# EWSII.net
KiCad netlist of a schematic drawn in EAGLE
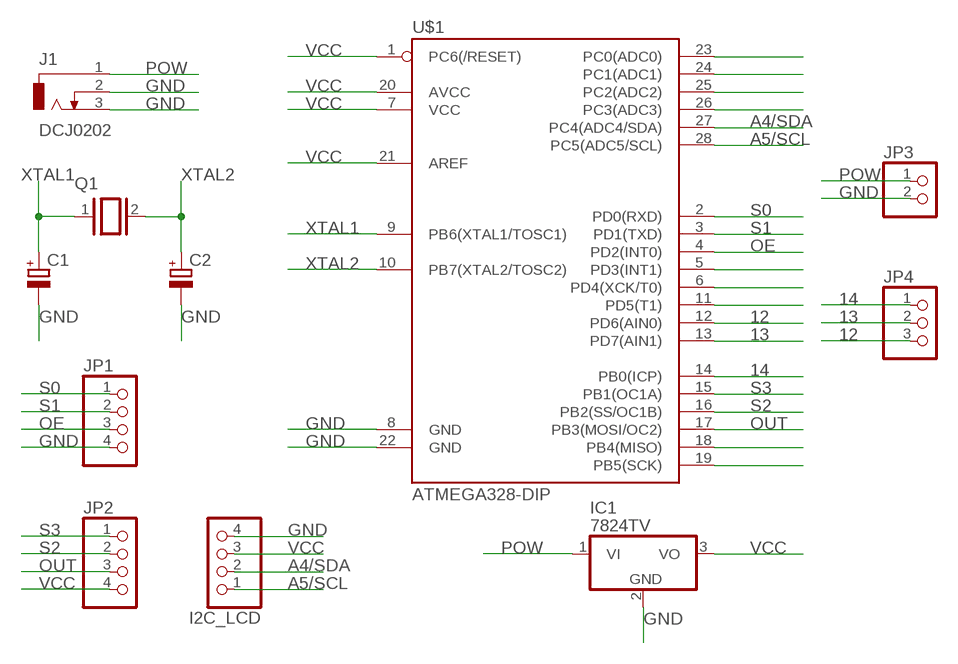
[diagram p0: schematic, sheet 1]

(export (version "E")
  (design (tool "Eeschema 10.0.6"))
  (components
    (comp (ref "C1")
      (value "CPOL-EUE2-5")
      (footprint "eagle-import:E2-5")
      (libsource (lib "eagle-import") (part "CPOL-EUE2-5"))
    )
    (comp (ref "C2")
      (value "CPOL-EUE2-5")
      (footprint "eagle-import:E2-5")
      (libsource (lib "eagle-import") (part "CPOL-EUE2-5"))
    )
    (comp (ref "I2C_LCD")
      (value "PINHD-1X4")
      (footprint "eagle-import:1X04")
      (libsource (lib "eagle-import") (part "PINHD-1X4"))
    )
    (comp (ref "IC1")
      (value "7824TV")
      (footprint "eagle-import:TO220V")
      (libsource (lib "eagle-import") (part "78TV24"))
    )
    (comp (ref "J1")
      (value "DCJ0202")
      (footprint "eagle-import:DCJ0202")
      (libsource (lib "eagle-import") (part "DCJ0202"))
    )
    (comp (ref "JP1")
      (value "PINHD-1X4")
      (footprint "eagle-import:1X04")
      (libsource (lib "eagle-import") (part "PINHD-1X4"))
    )
    (comp (ref "JP2")
      (value "PINHD-1X4")
      (footprint "eagle-import:1X04")
      (libsource (lib "eagle-import") (part "PINHD-1X4"))
    )
    (comp (ref "JP3")
      (value "PINHD-1X2")
      (footprint "eagle-import:1X02")
      (libsource (lib "eagle-import") (part "PINHD-1X2"))
    )
    (comp (ref "JP4")
      (value "PINHD-1X3")
      (footprint "eagle-import:1X03")
      (libsource (lib "eagle-import") (part "PINHD-1X3"))
    )
    (comp (ref "Q1")
      (value "XTAL/S")
      (footprint "eagle-import:QS")
      (libsource (lib "eagle-import") (part "XTAL/S"))
    )
    (comp (ref "U$1")
      (value "ATMEGA328-DIP")
      (footprint "eagle-import:DIP1016W53P254L3466H457Q28B")
      (libsource (lib "eagle-import") (part "ATMEGA328-DIP"))
    )
  )
  (nets
    (net (code "1") (name "/12") (class "Default")
      (node (ref "JP4") (pin "3") (pinfunction "3_3") (pintype "passive"))
      (node (ref "U$1") (pin "12") (pinfunction "PD6(AIN0)_12") (pintype "bidirectional"))
    )
    (net (code "2") (name "/13") (class "Default")
      (node (ref "JP4") (pin "2") (pinfunction "2_2") (pintype "passive"))
      (node (ref "U$1") (pin "13") (pinfunction "PD7(AIN1)_13") (pintype "bidirectional"))
    )
    (net (code "3") (name "/14") (class "Default")
      (node (ref "JP4") (pin "1") (pinfunction "1_1") (pintype "passive"))
      (node (ref "U$1") (pin "14") (pinfunction "PB0(ICP)_14") (pintype "bidirectional"))
    )
    (net (code "4") (name "/A4{slash}SDA") (class "Default")
      (node (ref "I2C_LCD") (pin "2") (pinfunction "2_2") (pintype "passive"))
      (node (ref "U$1") (pin "27") (pinfunction "PC4(ADC4/SDA)_27") (pintype "bidirectional"))
    )
    (net (code "5") (name "/A5{slash}SCL") (class "Default")
      (node (ref "I2C_LCD") (pin "1") (pinfunction "1_1") (pintype "passive"))
      (node (ref "U$1") (pin "28") (pinfunction "PC5(ADC5/SCL)_28") (pintype "bidirectional"))
    )
    (net (code "6") (name "/GND") (class "Default")
      (node (ref "C1") (pin "-") (pinfunction "-_-") (pintype "passive"))
      (node (ref "C2") (pin "-") (pinfunction "-_-") (pintype "passive"))
      (node (ref "I2C_LCD") (pin "4") (pinfunction "4_4") (pintype "passive"))
      (node (ref "IC1") (pin "2") (pinfunction "GND_2") (pintype "passive"))
      (node (ref "J1") (pin "2") (pinfunction "2_2") (pintype "passive"))
      (node (ref "J1") (pin "3") (pinfunction "3_3") (pintype "passive"))
      (node (ref "JP1") (pin "4") (pinfunction "4_4") (pintype "passive"))
      (node (ref "JP3") (pin "2") (pinfunction "2_2") (pintype "passive"))
      (node (ref "U$1") (pin "22") (pinfunction "GND_22") (pintype "bidirectional"))
      (node (ref "U$1") (pin "8") (pinfunction "GND_8") (pintype "bidirectional"))
    )
    (net (code "7") (name "/OE") (class "Default")
      (node (ref "JP1") (pin "3") (pinfunction "3_3") (pintype "passive"))
      (node (ref "U$1") (pin "4") (pinfunction "PD2(INT0)_4") (pintype "bidirectional"))
    )
    (net (code "8") (name "/OUT") (class "Default")
      (node (ref "JP2") (pin "3") (pinfunction "3_3") (pintype "passive"))
      (node (ref "U$1") (pin "17") (pinfunction "PB3(MOSI/OC2)_17") (pintype "bidirectional"))
    )
    (net (code "9") (name "/POW") (class "Default")
      (node (ref "IC1") (pin "1") (pinfunction "VI_1") (pintype "input"))
      (node (ref "J1") (pin "1") (pinfunction "1_1") (pintype "passive"))
      (node (ref "JP3") (pin "1") (pinfunction "1_1") (pintype "passive"))
    )
    (net (code "10") (name "/S0") (class "Default")
      (node (ref "JP1") (pin "1") (pinfunction "1_1") (pintype "passive"))
      (node (ref "U$1") (pin "2") (pinfunction "PD0(RXD)_2") (pintype "bidirectional"))
    )
    (net (code "11") (name "/S1") (class "Default")
      (node (ref "JP1") (pin "2") (pinfunction "2_2") (pintype "passive"))
      (node (ref "U$1") (pin "3") (pinfunction "PD1(TXD)_3") (pintype "bidirectional"))
    )
    (net (code "12") (name "/S2") (class "Default")
      (node (ref "JP2") (pin "2") (pinfunction "2_2") (pintype "passive"))
      (node (ref "U$1") (pin "16") (pinfunction "PB2(SS/OC1B)_16") (pintype "bidirectional"))
    )
    (net (code "13") (name "/S3") (class "Default")
      (node (ref "JP2") (pin "1") (pinfunction "1_1") (pintype "passive"))
      (node (ref "U$1") (pin "15") (pinfunction "PB1(OC1A)_15") (pintype "bidirectional"))
    )
    (net (code "14") (name "/VCC") (class "Default")
      (node (ref "I2C_LCD") (pin "3") (pinfunction "3_3") (pintype "passive"))
      (node (ref "IC1") (pin "3") (pinfunction "VO_3") (pintype "passive"))
      (node (ref "JP2") (pin "4") (pinfunction "4_4") (pintype "passive"))
      (node (ref "U$1") (pin "1") (pinfunction "PC6(/RESET)_1") (pintype "bidirectional"))
      (node (ref "U$1") (pin "20") (pinfunction "AVCC_20") (pintype "bidirectional"))
      (node (ref "U$1") (pin "21") (pinfunction "AREF_21") (pintype "bidirectional"))
      (node (ref "U$1") (pin "7") (pinfunction "VCC_7") (pintype "bidirectional"))
    )
    (net (code "15") (name "/XTAL1") (class "Default")
      (node (ref "C1") (pin "+") (pinfunction "+_+") (pintype "passive"))
      (node (ref "Q1") (pin "1") (pinfunction "1_1") (pintype "passive"))
      (node (ref "U$1") (pin "9") (pinfunction "PB6(XTAL1/TOSC1)_9") (pintype "bidirectional"))
    )
    (net (code "16") (name "/XTAL2") (class "Default")
      (node (ref "C2") (pin "+") (pinfunction "+_+") (pintype "passive"))
      (node (ref "Q1") (pin "2") (pinfunction "2_2") (pintype "passive"))
      (node (ref "U$1") (pin "10") (pinfunction "PB7(XTAL2/TOSC2)_10") (pintype "bidirectional"))
    )
    (net (code "17") (name "unconnected-(U$1-PB4(MISO)-Pad18)") (class "Default")
      (node (ref "U$1") (pin "18") (pinfunction "PB4(MISO)_18") (pintype "bidirectional"))
    )
    (net (code "18") (name "unconnected-(U$1-PB5(SCK)-Pad19)") (class "Default")
      (node (ref "U$1") (pin "19") (pinfunction "PB5(SCK)_19") (pintype "bidirectional"))
    )
    (net (code "19") (name "unconnected-(U$1-PC0(ADC0)-Pad23)") (class "Default")
      (node (ref "U$1") (pin "23") (pinfunction "PC0(ADC0)_23") (pintype "bidirectional"))
    )
    (net (code "20") (name "unconnected-(U$1-PC1(ADC1)-Pad24)") (class "Default")
      (node (ref "U$1") (pin "24") (pinfunction "PC1(ADC1)_24") (pintype "bidirectional"))
    )
    (net (code "21") (name "unconnected-(U$1-PC2(ADC2)-Pad25)") (class "Default")
      (node (ref "U$1") (pin "25") (pinfunction "PC2(ADC2)_25") (pintype "bidirectional"))
    )
    (net (code "22") (name "unconnected-(U$1-PC3(ADC3)-Pad26)") (class "Default")
      (node (ref "U$1") (pin "26") (pinfunction "PC3(ADC3)_26") (pintype "bidirectional"))
    )
    (net (code "23") (name "unconnected-(U$1-PD3(INT1)-Pad5)") (class "Default")
      (node (ref "U$1") (pin "5") (pinfunction "PD3(INT1)_5") (pintype "bidirectional"))
    )
    (net (code "24") (name "unconnected-(U$1-PD4(XCK{slash}T0)-Pad6)") (class "Default")
      (node (ref "U$1") (pin "6") (pinfunction "PD4(XCK/T0)_6") (pintype "bidirectional"))
    )
    (net (code "25") (name "unconnected-(U$1-PD5(T1)-Pad11)") (class "Default")
      (node (ref "U$1") (pin "11") (pinfunction "PD5(T1)_11") (pintype "bidirectional"))
    )
  )
)
